# TinyGController.net
KiCad netlist of a schematic drawn in EAGLE
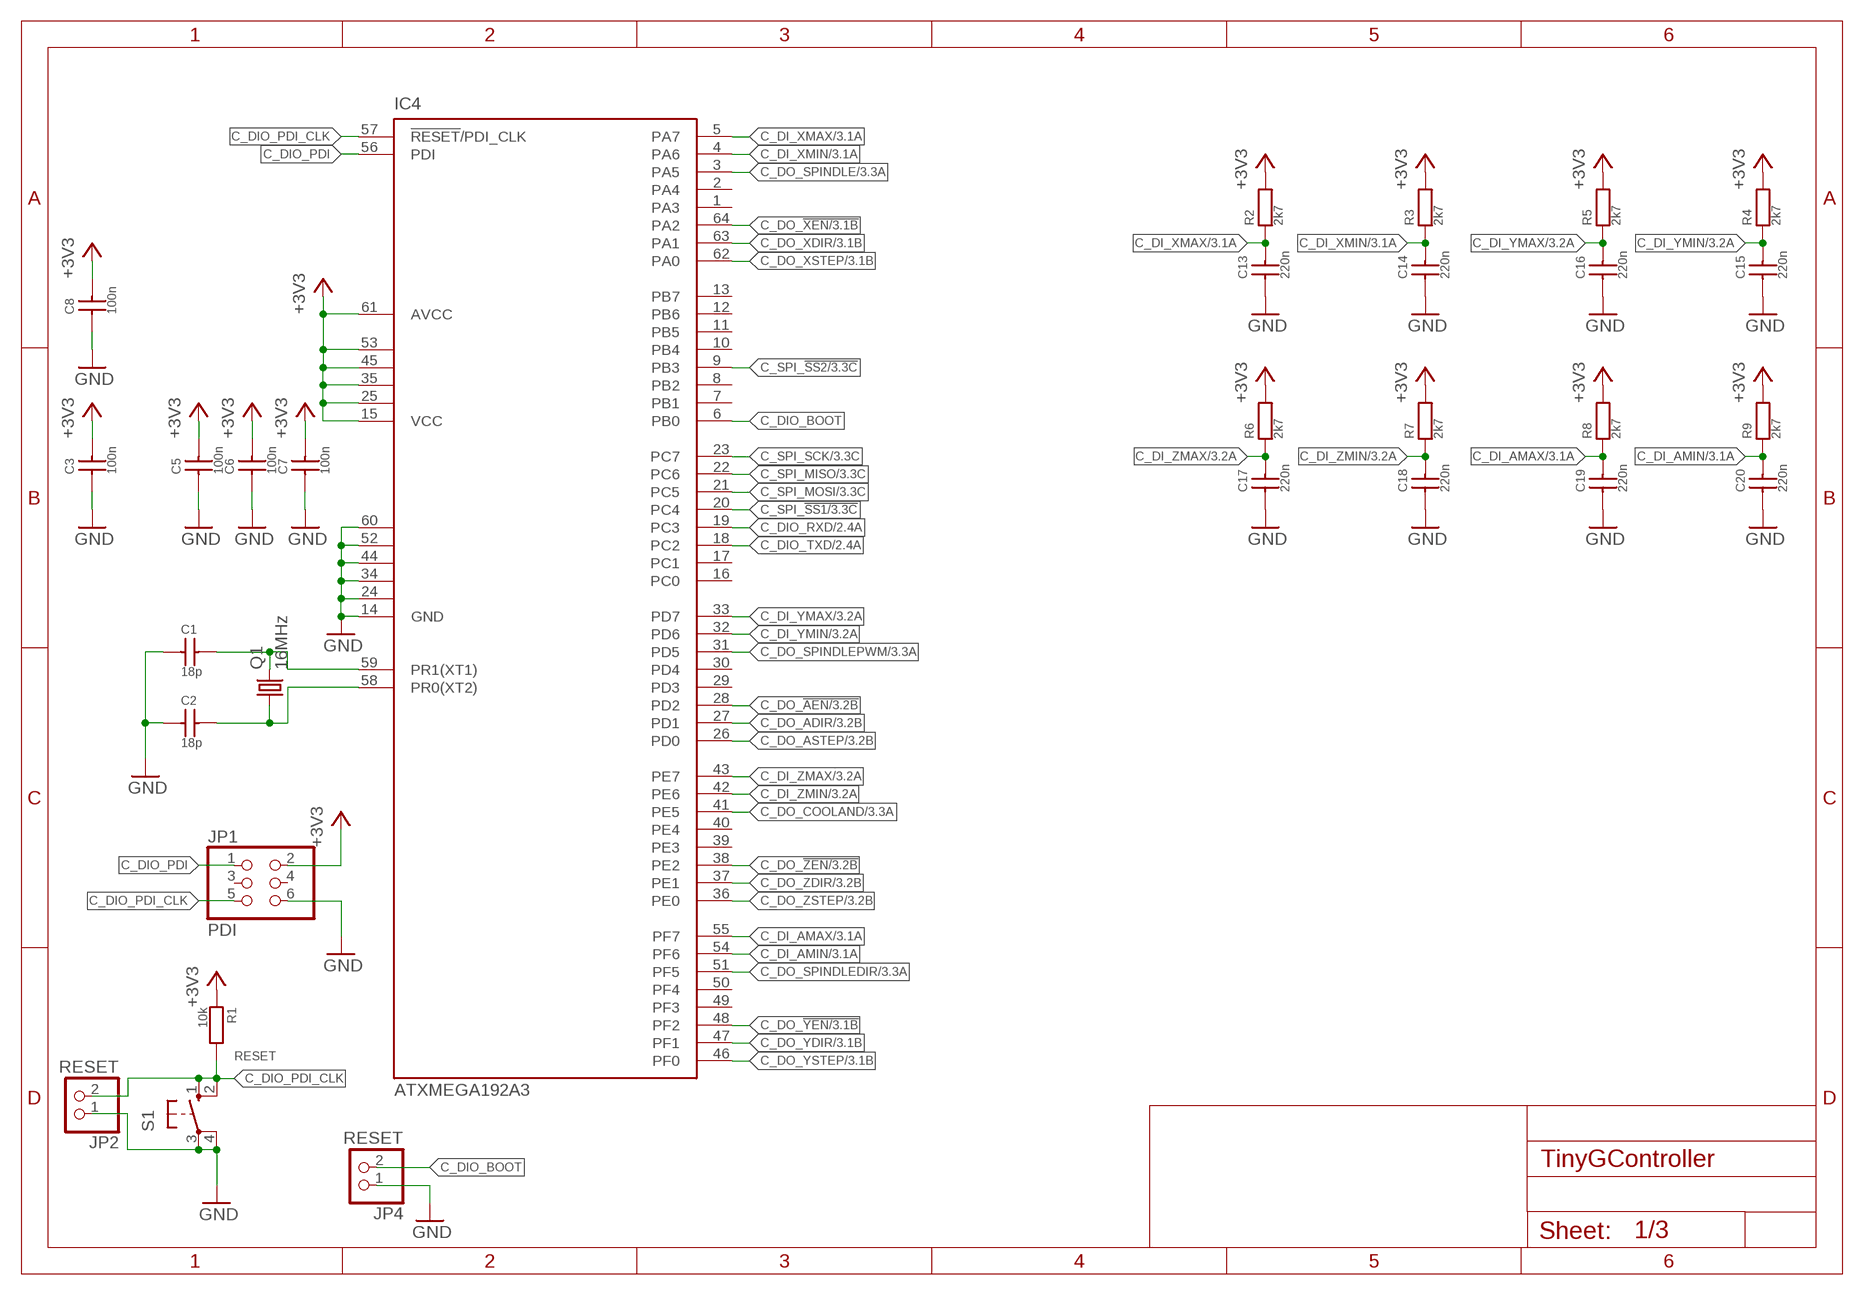
[diagram p0: schematic, sheet 1]
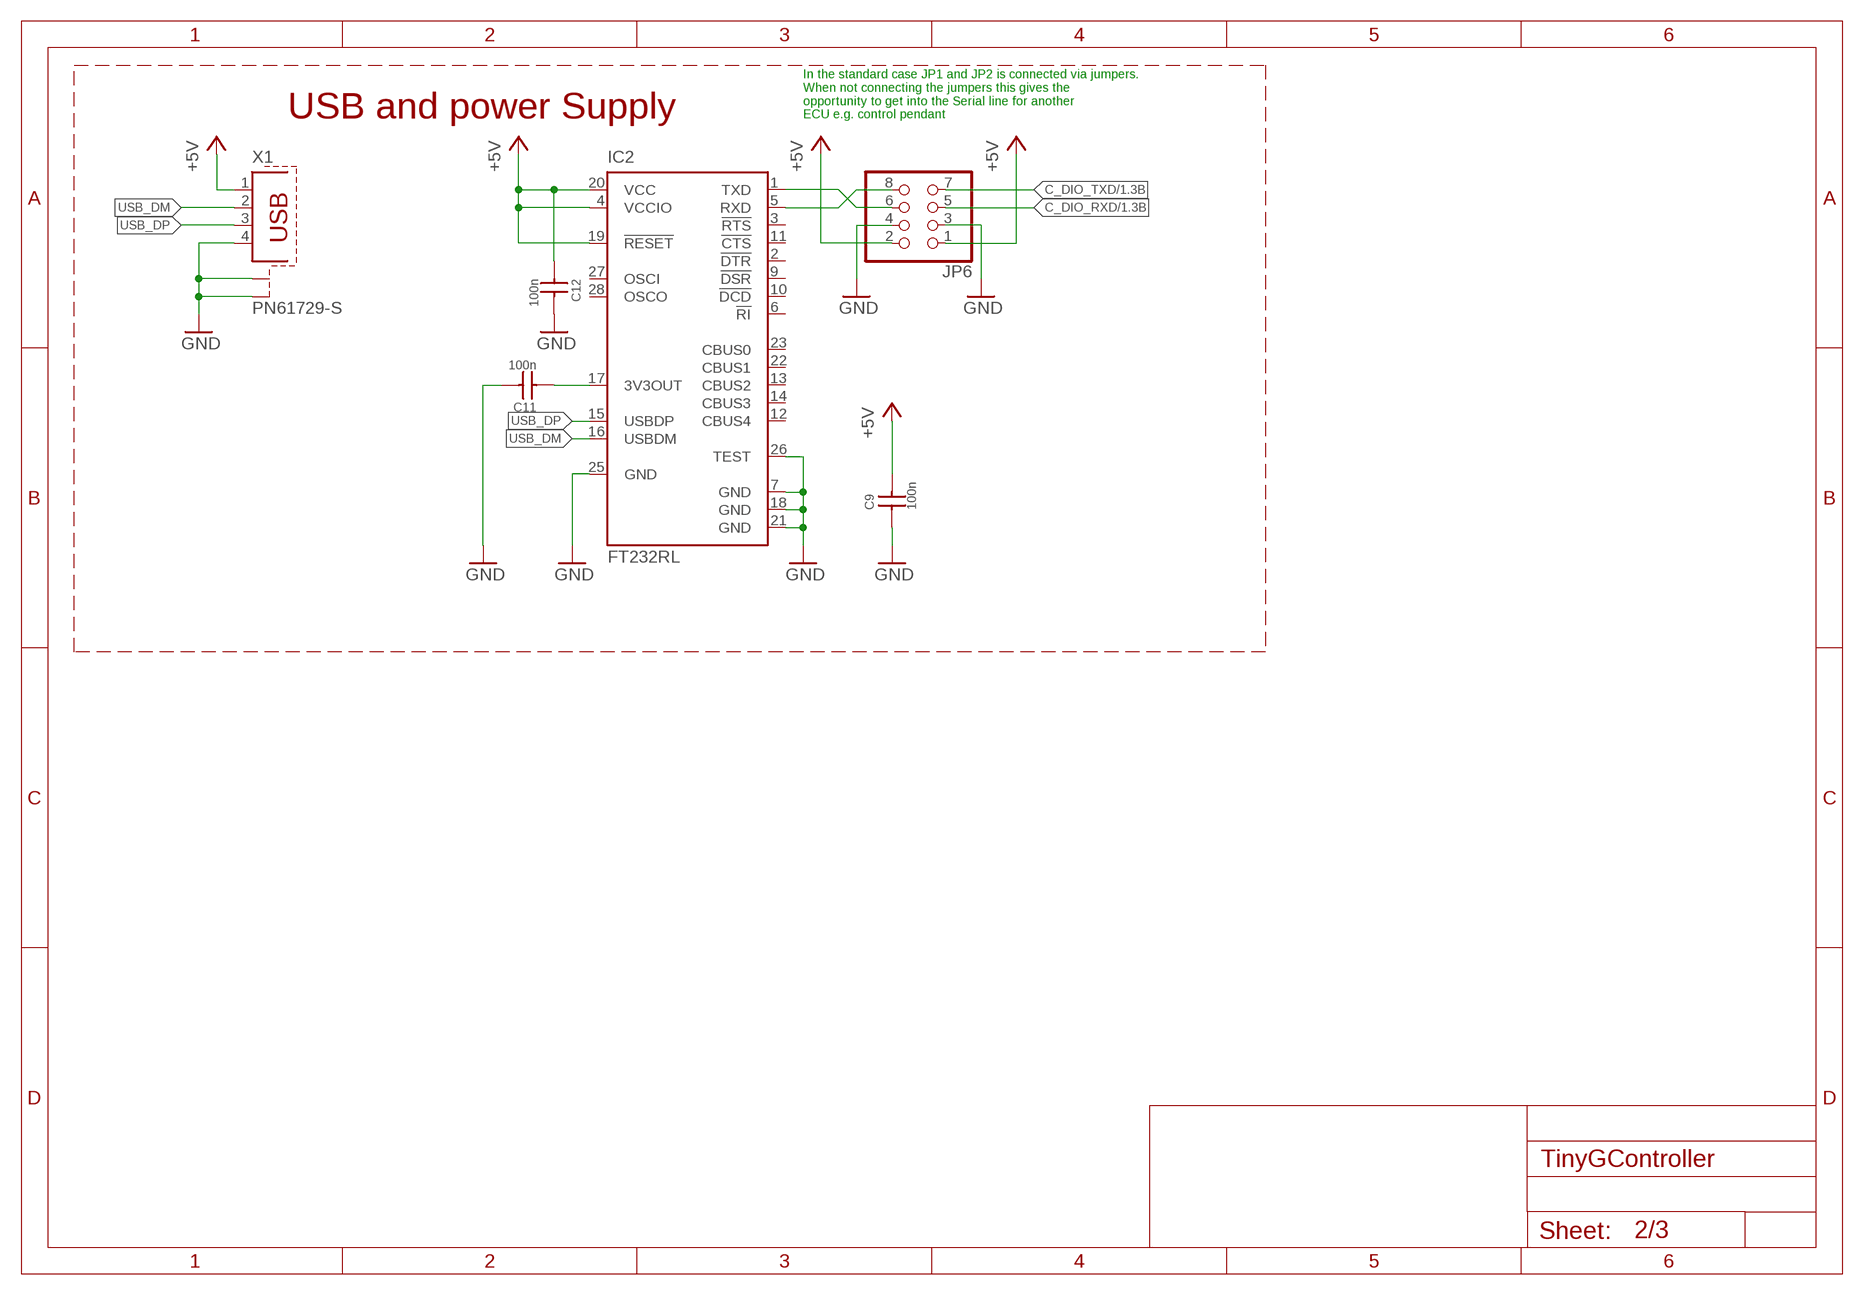
[diagram p1: schematic, sheet 2]
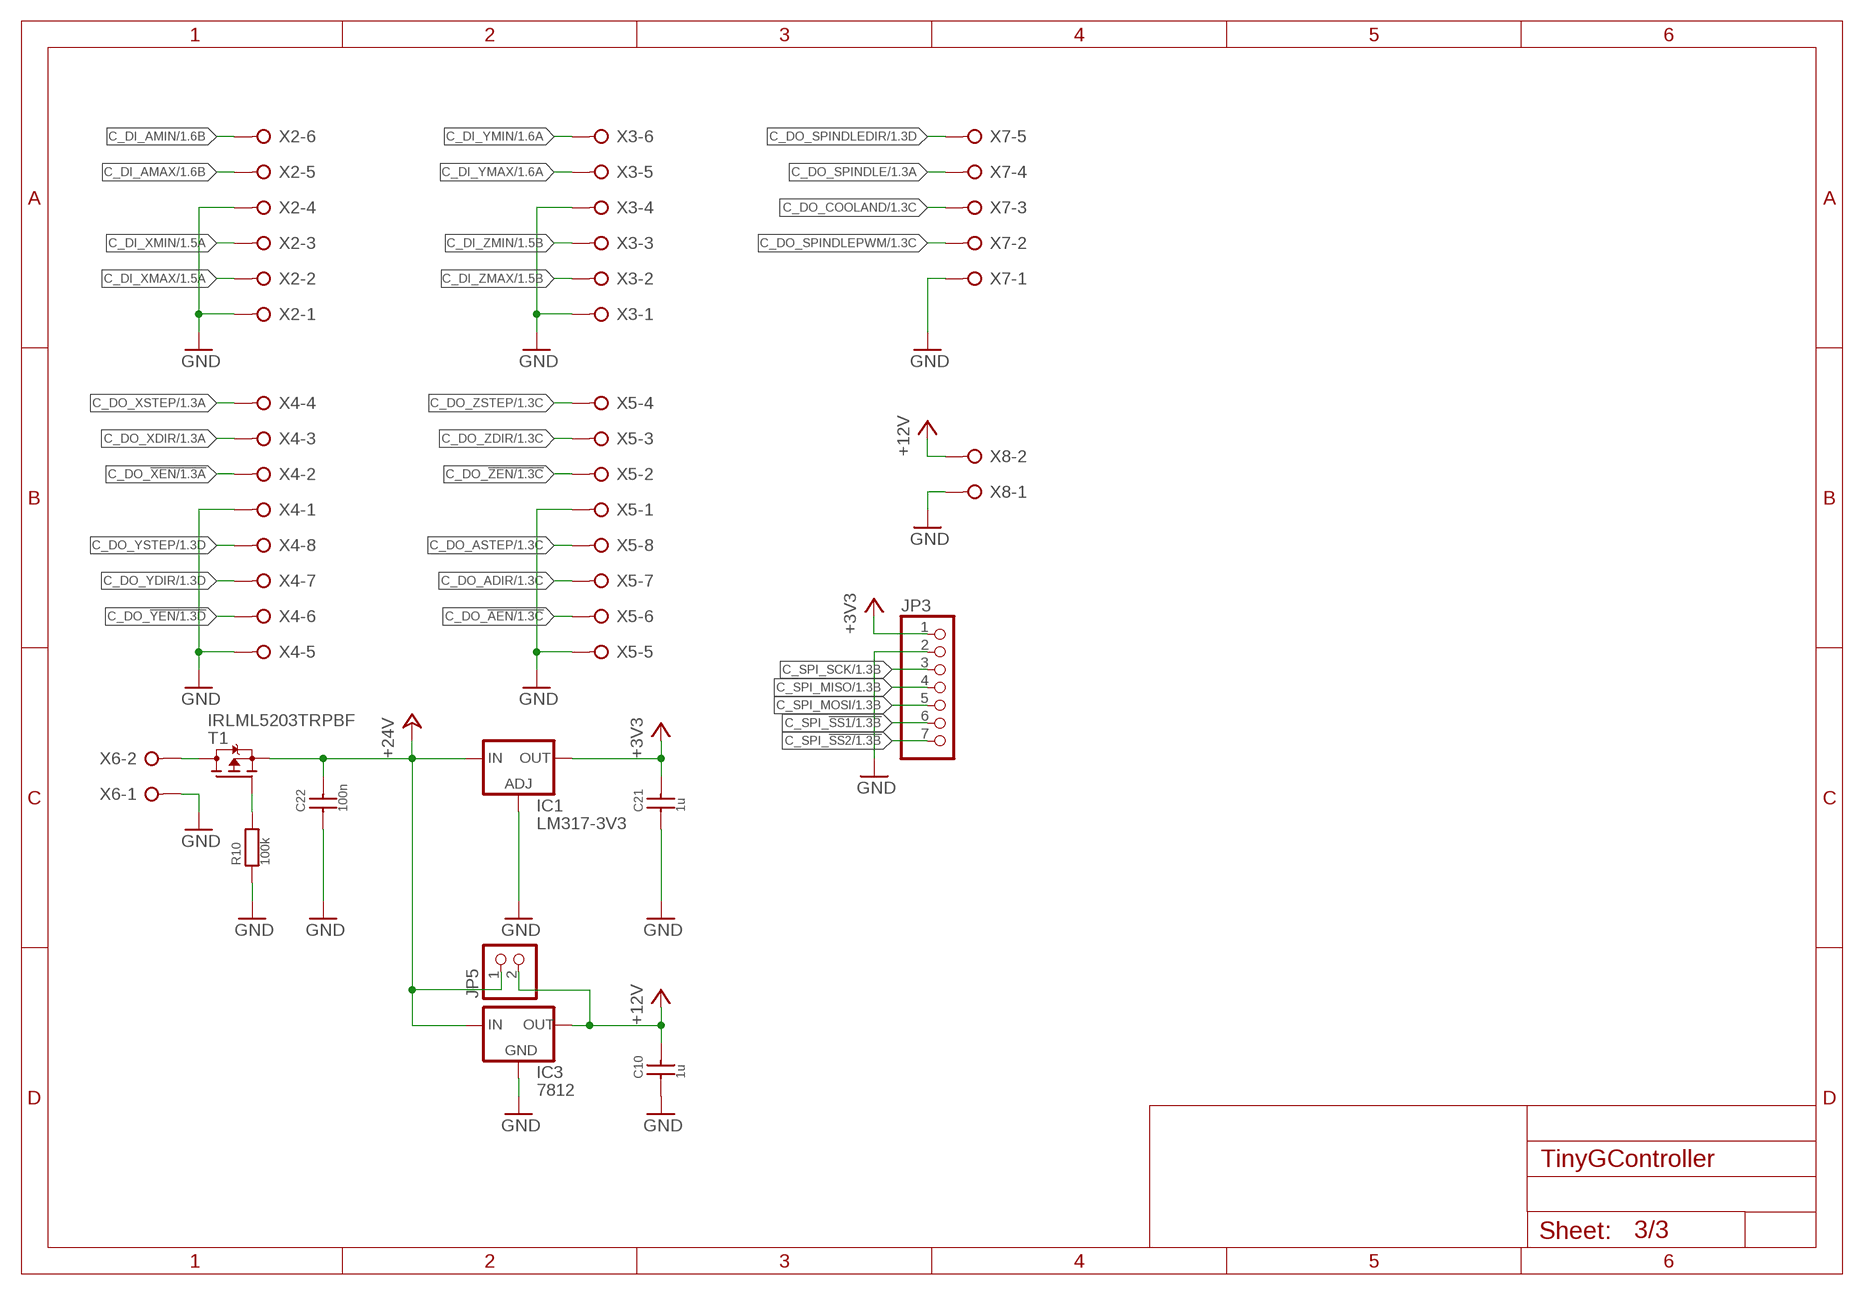
[diagram p2: schematic, sheet 3]

(export (version "E")
  (design (tool "Eeschema 10.0.6"))
  (components
    (comp (ref "C10")
      (value "1u")
      (footprint "eagle-import:C0805")
      (libsource (lib "eagle-import") (part "C_SMD0805"))
    )
    (comp (ref "C21")
      (value "1u")
      (footprint "eagle-import:C0805")
      (libsource (lib "eagle-import") (part "C_SMD0805"))
    )
    (comp (ref "C22")
      (value "100n")
      (footprint "eagle-import:C0805")
      (libsource (lib "eagle-import") (part "C_SMD0805"))
    )
    (comp (ref "IC1")
      (value "LM317-3V3")
      (footprint "eagle-import:SOT223")
      (libsource (lib "eagle-import") (part "LM317?MBSTT3"))
    )
    (comp (ref "IC3")
      (value "7812")
      (footprint "eagle-import:78XXS")
      (libsource (lib "eagle-import") (part "78XXS"))
    )
    (comp (ref "JP3")
      (value "PINHD-1X7")
      (footprint "eagle-import:1X07")
      (libsource (lib "eagle-import") (part "PINHD-1X7"))
    )
    (comp (ref "JP5")
      (value "PINHD-1X2")
      (footprint "eagle-import:1X02")
      (libsource (lib "eagle-import") (part "PINHD-1X2"))
    )
    (comp (ref "R10")
      (value "100k")
      (footprint "eagle-import:R0603")
      (libsource (lib "eagle-import") (part "R0603"))
    )
    (comp (ref "T1")
      (value "IRLML5203TRPBF")
      (footprint "eagle-import:SOT23")
      (libsource (lib "eagle-import") (part "IRLML5203TRPBF"))
    )
    (comp (ref "X2")
      (value "W237-06P")
      (footprint "eagle-import:W237-6P")
      (libsource (lib "eagle-import") (part "W237-06P"))
    )
    (comp (ref "X3")
      (value "W237-06P")
      (footprint "eagle-import:W237-6P")
      (libsource (lib "eagle-import") (part "W237-06P"))
    )
    (comp (ref "X4")
      (value "W237-08P")
      (footprint "eagle-import:W237-8P")
      (libsource (lib "eagle-import") (part "W237-08P"))
    )
    (comp (ref "X5")
      (value "W237-08P")
      (footprint "eagle-import:W237-8P")
      (libsource (lib "eagle-import") (part "W237-08P"))
    )
    (comp (ref "X6")
      (value "W237-02P")
      (footprint "eagle-import:W237-132")
      (libsource (lib "eagle-import") (part "W237-02P"))
    )
    (comp (ref "X7")
      (value "W237-05P")
      (footprint "eagle-import:W237-5P")
      (libsource (lib "eagle-import") (part "W237-05P"))
    )
    (comp (ref "X8")
      (value "W237-02P")
      (footprint "eagle-import:W237-132")
      (libsource (lib "eagle-import") (part "W237-02P"))
    )
    (comp (ref "C9")
      (value "100n")
      (footprint "eagle-import:C0603")
      (libsource (lib "eagle-import") (part "C_SMD0603"))
    )
    (comp (ref "C11")
      (value "100n")
      (footprint "eagle-import:C0603")
      (libsource (lib "eagle-import") (part "C_SMD0603"))
    )
    (comp (ref "C12")
      (value "100n")
      (footprint "eagle-import:C0603")
      (libsource (lib "eagle-import") (part "C_SMD0603"))
    )
    (comp (ref "IC2")
      (value "FT232RL")
      (footprint "eagle-import:SSOP28")
      (libsource (lib "eagle-import") (part "FT232RL"))
    )
    (comp (ref "JP6")
      (value "PINHD-2X4")
      (footprint "eagle-import:2X04")
      (libsource (lib "eagle-import") (part "PINHD-2X4"))
    )
    (comp (ref "X1")
      (value "PN61729-S")
      (footprint "eagle-import:PN61729-S")
      (libsource (lib "eagle-import") (part "PN61729-S"))
    )
    (comp (ref "C1")
      (value "18p")
      (footprint "eagle-import:C0603")
      (libsource (lib "eagle-import") (part "C_SMD0603"))
    )
    (comp (ref "C2")
      (value "18p")
      (footprint "eagle-import:C0603")
      (libsource (lib "eagle-import") (part "C_SMD0603"))
    )
    (comp (ref "C3")
      (value "100n")
      (footprint "eagle-import:C0603")
      (libsource (lib "eagle-import") (part "C_SMD0603"))
    )
    (comp (ref "C5")
      (value "100n")
      (footprint "eagle-import:C0603")
      (libsource (lib "eagle-import") (part "C_SMD0603"))
    )
    (comp (ref "C6")
      (value "100n")
      (footprint "eagle-import:C0603")
      (libsource (lib "eagle-import") (part "C_SMD0603"))
    )
    (comp (ref "C7")
      (value "100n")
      (footprint "eagle-import:C0603")
      (libsource (lib "eagle-import") (part "C_SMD0603"))
    )
    (comp (ref "C8")
      (value "100n")
      (footprint "eagle-import:C0603")
      (libsource (lib "eagle-import") (part "C_SMD0603"))
    )
    (comp (ref "C13")
      (value "220n")
      (footprint "eagle-import:C0805")
      (libsource (lib "eagle-import") (part "C_SMD0805"))
    )
    (comp (ref "C14")
      (value "220n")
      (footprint "eagle-import:C0805")
      (libsource (lib "eagle-import") (part "C_SMD0805"))
    )
    (comp (ref "C15")
      (value "220n")
      (footprint "eagle-import:C0805")
      (libsource (lib "eagle-import") (part "C_SMD0805"))
    )
    (comp (ref "C16")
      (value "220n")
      (footprint "eagle-import:C0805")
      (libsource (lib "eagle-import") (part "C_SMD0805"))
    )
    (comp (ref "C17")
      (value "220n")
      (footprint "eagle-import:C0805")
      (libsource (lib "eagle-import") (part "C_SMD0805"))
    )
    (comp (ref "C18")
      (value "220n")
      (footprint "eagle-import:C0805")
      (libsource (lib "eagle-import") (part "C_SMD0805"))
    )
    (comp (ref "C19")
      (value "220n")
      (footprint "eagle-import:C0805")
      (libsource (lib "eagle-import") (part "C_SMD0805"))
    )
    (comp (ref "C20")
      (value "220n")
      (footprint "eagle-import:C0805")
      (libsource (lib "eagle-import") (part "C_SMD0805"))
    )
    (comp (ref "IC4")
      (value "ATXMEGA192A3")
      (footprint "eagle-import:TQFP64-0.8MM")
      (libsource (lib "eagle-import") (part "ATXMEGA192A3"))
    )
    (comp (ref "JP1")
      (value "PDI")
      (footprint "eagle-import:2X03")
      (libsource (lib "eagle-import") (part "PINHD-2X3"))
    )
    (comp (ref "JP2")
      (value "RESET")
      (footprint "eagle-import:1X02")
      (libsource (lib "eagle-import") (part "PINHD-1X2"))
    )
    (comp (ref "JP4")
      (value "RESET")
      (footprint "eagle-import:1X02")
      (libsource (lib "eagle-import") (part "PINHD-1X2"))
    )
    (comp (ref "Q1")
      (value "16MHz")
      (footprint "eagle-import:HC49_USSM")
      (libsource (lib "eagle-import") (part "ATS073ASM-1"))
    )
    (comp (ref "R1")
      (value "10k")
      (footprint "eagle-import:R0603")
      (libsource (lib "eagle-import") (part "R0603"))
    )
    (comp (ref "R2")
      (value "2k7")
      (footprint "eagle-import:R0603")
      (libsource (lib "eagle-import") (part "R0603"))
    )
    (comp (ref "R3")
      (value "2k7")
      (footprint "eagle-import:R0603")
      (libsource (lib "eagle-import") (part "R0603"))
    )
    (comp (ref "R4")
      (value "2k7")
      (footprint "eagle-import:R0603")
      (libsource (lib "eagle-import") (part "R0603"))
    )
    (comp (ref "R5")
      (value "2k7")
      (footprint "eagle-import:R0603")
      (libsource (lib "eagle-import") (part "R0603"))
    )
    (comp (ref "R6")
      (value "2k7")
      (footprint "eagle-import:R0603")
      (libsource (lib "eagle-import") (part "R0603"))
    )
    (comp (ref "R7")
      (value "2k7")
      (footprint "eagle-import:R0603")
      (libsource (lib "eagle-import") (part "R0603"))
    )
    (comp (ref "R8")
      (value "2k7")
      (footprint "eagle-import:R0603")
      (libsource (lib "eagle-import") (part "R0603"))
    )
    (comp (ref "R9")
      (value "2k7")
      (footprint "eagle-import:R0603")
      (libsource (lib "eagle-import") (part "R0603"))
    )
    (comp (ref "S1")
      (value "10-XX")
      (footprint "eagle-import:B3F-10XX")
      (fields (field (name "MPN") "B3F-1000"))
      (libsource (lib "eagle-import") (part "10-XX"))
    )
  )
  (nets
    (net (code "1") (name "+3V3") (class "Default")
      (node (ref "C21") (pin "2") (pinfunction "P$2_2") (pintype "passive"))
      (node (ref "C3") (pin "2") (pinfunction "P$2_2") (pintype "passive"))
      (node (ref "C5") (pin "2") (pinfunction "P$2_2") (pintype "passive"))
      (node (ref "C6") (pin "2") (pinfunction "P$2_2") (pintype "passive"))
      (node (ref "C7") (pin "2") (pinfunction "P$2_2") (pintype "passive"))
      (node (ref "C8") (pin "2") (pinfunction "P$2_2") (pintype "passive"))
      (node (ref "IC1") (pin "4") (pinfunction "OUT_4") (pintype "passive"))
      (node (ref "IC4") (pin "15") (pinfunction "VCC_15") (pintype "power_in"))
      (node (ref "IC4") (pin "25") (pinfunction "VCC1_25") (pintype "power_in"))
      (node (ref "IC4") (pin "35") (pinfunction "VCC2_35") (pintype "power_in"))
      (node (ref "IC4") (pin "45") (pinfunction "VCC3_45") (pintype "power_in"))
      (node (ref "IC4") (pin "53") (pinfunction "VCC4_53") (pintype "power_in"))
      (node (ref "IC4") (pin "61") (pinfunction "AVCC_61") (pintype "power_in"))
      (node (ref "JP1") (pin "2") (pinfunction "2_2") (pintype "passive"))
      (node (ref "JP3") (pin "1") (pinfunction "1_1") (pintype "passive"))
      (node (ref "R1") (pin "1") (pinfunction "P$1_1") (pintype "passive"))
      (node (ref "R2") (pin "2") (pinfunction "P$2_2") (pintype "passive"))
      (node (ref "R3") (pin "2") (pinfunction "P$2_2") (pintype "passive"))
      (node (ref "R4") (pin "2") (pinfunction "P$2_2") (pintype "passive"))
      (node (ref "R5") (pin "2") (pinfunction "P$2_2") (pintype "passive"))
      (node (ref "R6") (pin "2") (pinfunction "P$2_2") (pintype "passive"))
      (node (ref "R7") (pin "2") (pinfunction "P$2_2") (pintype "passive"))
      (node (ref "R8") (pin "2") (pinfunction "P$2_2") (pintype "passive"))
      (node (ref "R9") (pin "2") (pinfunction "P$2_2") (pintype "passive"))
    )
    (net (code "2") (name "+5V") (class "Default")
      (node (ref "C12") (pin "1") (pinfunction "P$1_1") (pintype "passive"))
      (node (ref "C9") (pin "2") (pinfunction "P$2_2") (pintype "passive"))
      (node (ref "IC2") (pin "19") (pinfunction "~{RESET}_19") (pintype "input"))
      (node (ref "IC2") (pin "20") (pinfunction "VCC_20") (pintype "power_in"))
      (node (ref "IC2") (pin "4") (pinfunction "VCCIO_4") (pintype "power_in"))
      (node (ref "JP6") (pin "1") (pinfunction "1_1") (pintype "passive"))
      (node (ref "JP6") (pin "2") (pinfunction "2_2") (pintype "passive"))
      (node (ref "X1") (pin "1") (pinfunction "1_1") (pintype "passive"))
    )
    (net (code "3") (name "+12V") (class "Default")
      (node (ref "C10") (pin "2") (pinfunction "P$2_2") (pintype "passive"))
      (node (ref "IC3") (pin "OUT") (pinfunction "OUT_OUT") (pintype "passive"))
      (node (ref "JP5") (pin "2") (pinfunction "2_2") (pintype "passive"))
      (node (ref "X8") (pin "2") (pinfunction "KL_2") (pintype "passive"))
    )
    (net (code "4") (name "+24V") (class "Default")
      (node (ref "C22") (pin "2") (pinfunction "P$2_2") (pintype "passive"))
      (node (ref "IC1") (pin "3") (pinfunction "IN_3") (pintype "input"))
      (node (ref "IC3") (pin "IN") (pinfunction "IN_IN") (pintype "input"))
      (node (ref "JP5") (pin "1") (pinfunction "1_1") (pintype "passive"))
      (node (ref "T1") (pin "2") (pinfunction "S_2") (pintype "passive"))
    )
    (net (code "5") (name "C_DIO_BOOT") (class "Default")
      (node (ref "IC4") (pin "6") (pinfunction "PB0_6") (pintype "bidirectional"))
      (node (ref "JP4") (pin "2") (pinfunction "2_2") (pintype "passive"))
    )
    (net (code "6") (name "C_DIO_PDI") (class "Default")
      (node (ref "IC4") (pin "56") (pinfunction "PDI_56") (pintype "input"))
      (node (ref "JP1") (pin "1") (pinfunction "1_1") (pintype "passive"))
    )
    (net (code "7") (name "C_DIO_PDI_CLK") (class "Default")
      (node (ref "IC4") (pin "57") (pinfunction "~{RESET}/PDI_CLK_57") (pintype "input"))
      (node (ref "JP1") (pin "5") (pinfunction "5_5") (pintype "passive"))
      (node (ref "JP2") (pin "2") (pinfunction "2_2") (pintype "passive"))
      (node (ref "R1") (pin "2") (pinfunction "P$2_2") (pintype "passive"))
      (node (ref "S1") (pin "1") (pinfunction "S_1") (pintype "passive"))
      (node (ref "S1") (pin "2") (pinfunction "S1_2") (pintype "passive"))
    )
    (net (code "8") (name "C_DIO_RXD") (class "Default")
      (node (ref "IC4") (pin "19") (pinfunction "PC3_19") (pintype "bidirectional"))
      (node (ref "JP6") (pin "5") (pinfunction "5_5") (pintype "passive"))
    )
    (net (code "9") (name "C_DIO_TXD") (class "Default")
      (node (ref "IC4") (pin "18") (pinfunction "PC2_18") (pintype "bidirectional"))
      (node (ref "JP6") (pin "7") (pinfunction "7_7") (pintype "passive"))
    )
    (net (code "10") (name "C_DI_AMAX") (class "Default")
      (node (ref "C19") (pin "2") (pinfunction "P$2_2") (pintype "passive"))
      (node (ref "IC4") (pin "55") (pinfunction "PF7_55") (pintype "bidirectional"))
      (node (ref "R8") (pin "1") (pinfunction "P$1_1") (pintype "passive"))
      (node (ref "X2") (pin "5") (pinfunction "KL_5") (pintype "passive"))
    )
    (net (code "11") (name "C_DI_AMIN") (class "Default")
      (node (ref "C20") (pin "2") (pinfunction "P$2_2") (pintype "passive"))
      (node (ref "IC4") (pin "54") (pinfunction "PF6_54") (pintype "bidirectional"))
      (node (ref "R9") (pin "1") (pinfunction "P$1_1") (pintype "passive"))
      (node (ref "X2") (pin "6") (pinfunction "KL_6") (pintype "passive"))
    )
    (net (code "12") (name "C_DI_XMAX") (class "Default")
      (node (ref "C13") (pin "2") (pinfunction "P$2_2") (pintype "passive"))
      (node (ref "IC4") (pin "5") (pinfunction "PA7_5") (pintype "bidirectional"))
      (node (ref "R2") (pin "1") (pinfunction "P$1_1") (pintype "passive"))
      (node (ref "X2") (pin "2") (pinfunction "KL_2") (pintype "passive"))
    )
    (net (code "13") (name "C_DI_XMIN") (class "Default")
      (node (ref "C14") (pin "2") (pinfunction "P$2_2") (pintype "passive"))
      (node (ref "IC4") (pin "4") (pinfunction "PA6_4") (pintype "bidirectional"))
      (node (ref "R3") (pin "1") (pinfunction "P$1_1") (pintype "passive"))
      (node (ref "X2") (pin "3") (pinfunction "KL_3") (pintype "passive"))
    )
    (net (code "14") (name "C_DI_YMAX") (class "Default")
      (node (ref "C16") (pin "2") (pinfunction "P$2_2") (pintype "passive"))
      (node (ref "IC4") (pin "33") (pinfunction "PD7_33") (pintype "bidirectional"))
      (node (ref "R5") (pin "1") (pinfunction "P$1_1") (pintype "passive"))
      (node (ref "X3") (pin "5") (pinfunction "KL_5") (pintype "passive"))
    )
    (net (code "15") (name "C_DI_YMIN") (class "Default")
      (node (ref "C15") (pin "2") (pinfunction "P$2_2") (pintype "passive"))
      (node (ref "IC4") (pin "32") (pinfunction "PD6_32") (pintype "bidirectional"))
      (node (ref "R4") (pin "1") (pinfunction "P$1_1") (pintype "passive"))
      (node (ref "X3") (pin "6") (pinfunction "KL_6") (pintype "passive"))
    )
    (net (code "16") (name "C_DI_ZMAX") (class "Default")
      (node (ref "C17") (pin "2") (pinfunction "P$2_2") (pintype "passive"))
      (node (ref "IC4") (pin "43") (pinfunction "PE7_43") (pintype "bidirectional"))
      (node (ref "R6") (pin "1") (pinfunction "P$1_1") (pintype "passive"))
      (node (ref "X3") (pin "2") (pinfunction "KL_2") (pintype "passive"))
    )
    (net (code "17") (name "C_DI_ZMIN") (class "Default")
      (node (ref "C18") (pin "2") (pinfunction "P$2_2") (pintype "passive"))
      (node (ref "IC4") (pin "42") (pinfunction "PE6_42") (pintype "bidirectional"))
      (node (ref "R7") (pin "1") (pinfunction "P$1_1") (pintype "passive"))
      (node (ref "X3") (pin "3") (pinfunction "KL_3") (pintype "passive"))
    )
    (net (code "18") (name "C_DO_ADIR") (class "Default")
      (node (ref "IC4") (pin "27") (pinfunction "PD1_27") (pintype "bidirectional"))
      (node (ref "X5") (pin "7") (pinfunction "KL_7") (pintype "passive"))
    )
    (net (code "19") (name "C_DO_ASTEP") (class "Default")
      (node (ref "IC4") (pin "26") (pinfunction "PD0_26") (pintype "bidirectional"))
      (node (ref "X5") (pin "8") (pinfunction "KL_8") (pintype "passive"))
    )
    (net (code "20") (name "C_DO_COOLAND") (class "Default")
      (node (ref "IC4") (pin "41") (pinfunction "PE5_41") (pintype "bidirectional"))
      (node (ref "X7") (pin "3") (pinfunction "KL_3") (pintype "passive"))
    )
    (net (code "21") (name "C_DO_SPINDLE") (class "Default")
      (node (ref "IC4") (pin "3") (pinfunction "PA5_3") (pintype "bidirectional"))
      (node (ref "X7") (pin "4") (pinfunction "KL_4") (pintype "passive"))
    )
    (net (code "22") (name "C_DO_SPINDLEDIR") (class "Default")
      (node (ref "IC4") (pin "51") (pinfunction "PF5_51") (pintype "bidirectional"))
      (node (ref "X7") (pin "5") (pinfunction "KL_5") (pintype "passive"))
    )
    (net (code "23") (name "C_DO_SPINDLEPWM") (class "Default")
      (node (ref "IC4") (pin "31") (pinfunction "PD5_31") (pintype "bidirectional"))
      (node (ref "X7") (pin "2") (pinfunction "KL_2") (pintype "passive"))
    )
    (net (code "24") (name "C_DO_XDIR") (class "Default")
      (node (ref "IC4") (pin "63") (pinfunction "PA1_63") (pintype "bidirectional"))
      (node (ref "X4") (pin "3") (pinfunction "KL_3") (pintype "passive"))
    )
    (net (code "25") (name "C_DO_XSTEP") (class "Default")
      (node (ref "IC4") (pin "62") (pinfunction "PA0_62") (pintype "bidirectional"))
      (node (ref "X4") (pin "4") (pinfunction "KL_4") (pintype "passive"))
    )
    (net (code "26") (name "C_DO_YDIR") (class "Default")
      (node (ref "IC4") (pin "47") (pinfunction "PF1_47") (pintype "bidirectional"))
      (node (ref "X4") (pin "7") (pinfunction "KL_7") (pintype "passive"))
    )
    (net (code "27") (name "C_DO_YSTEP") (class "Default")
      (node (ref "IC4") (pin "46") (pinfunction "PF0_46") (pintype "bidirectional"))
      (node (ref "X4") (pin "8") (pinfunction "KL_8") (pintype "passive"))
    )
    (net (code "28") (name "C_DO_ZDIR") (class "Default")
      (node (ref "IC4") (pin "37") (pinfunction "PE1_37") (pintype "bidirectional"))
      (node (ref "X5") (pin "3") (pinfunction "KL_3") (pintype "passive"))
    )
    (net (code "29") (name "C_DO_ZSTEP") (class "Default")
      (node (ref "IC4") (pin "36") (pinfunction "PE0_36") (pintype "bidirectional"))
      (node (ref "X5") (pin "4") (pinfunction "KL_4") (pintype "passive"))
    )
    (net (code "30") (name "C_DO_~{AEN}") (class "Default")
      (node (ref "IC4") (pin "28") (pinfunction "PD2_28") (pintype "bidirectional"))
      (node (ref "X5") (pin "6") (pinfunction "KL_6") (pintype "passive"))
    )
    (net (code "31") (name "C_DO_~{XEN}") (class "Default")
      (node (ref "IC4") (pin "64") (pinfunction "PA2_64") (pintype "bidirectional"))
      (node (ref "X4") (pin "2") (pinfunction "KL_2") (pintype "passive"))
    )
    (net (code "32") (name "C_DO_~{YEN}") (class "Default")
      (node (ref "IC4") (pin "48") (pinfunction "PF2_48") (pintype "bidirectional"))
      (node (ref "X4") (pin "6") (pinfunction "KL_6") (pintype "passive"))
    )
    (net (code "33") (name "C_DO_~{ZEN}") (class "Default")
      (node (ref "IC4") (pin "38") (pinfunction "PE2_38") (pintype "bidirectional"))
      (node (ref "X5") (pin "2") (pinfunction "KL_2") (pintype "passive"))
    )
    (net (code "34") (name "C_SPI_MISO") (class "Default")
      (node (ref "IC4") (pin "22") (pinfunction "PC6_22") (pintype "bidirectional"))
      (node (ref "JP3") (pin "4") (pinfunction "4_4") (pintype "passive"))
    )
    (net (code "35") (name "C_SPI_MOSI") (class "Default")
      (node (ref "IC4") (pin "21") (pinfunction "PC5_21") (pintype "bidirectional"))
      (node (ref "JP3") (pin "5") (pinfunction "5_5") (pintype "passive"))
    )
    (net (code "36") (name "C_SPI_SCK") (class "Default")
      (node (ref "IC4") (pin "23") (pinfunction "PC7_23") (pintype "bidirectional"))
      (node (ref "JP3") (pin "3") (pinfunction "3_3") (pintype "passive"))
    )
    (net (code "37") (name "C_SPI_~{SS1}") (class "Default")
      (node (ref "IC4") (pin "20") (pinfunction "PC4_20") (pintype "bidirectional"))
      (node (ref "JP3") (pin "6") (pinfunction "6_6") (pintype "passive"))
    )
    (net (code "38") (name "C_SPI_~{SS2}") (class "Default")
      (node (ref "IC4") (pin "9") (pinfunction "PB3_9") (pintype "bidirectional"))
      (node (ref "JP3") (pin "7") (pinfunction "7_7") (pintype "passive"))
    )
    (net (code "39") (name "GND") (class "Default")
      (node (ref "C1") (pin "1") (pinfunction "P$1_1") (pintype "passive"))
      (node (ref "C10") (pin "1") (pinfunction "P$1_1") (pintype "passive"))
      (node (ref "C11") (pin "2") (pinfunction "P$2_2") (pintype "passive"))
      (node (ref "C12") (pin "2") (pinfunction "P$2_2") (pintype "passive"))
      (node (ref "C13") (pin "1") (pinfunction "P$1_1") (pintype "passive"))
      (node (ref "C14") (pin "1") (pinfunction "P$1_1") (pintype "passive"))
      (node (ref "C15") (pin "1") (pinfunction "P$1_1") (pintype "passive"))
      (node (ref "C16") (pin "1") (pinfunction "P$1_1") (pintype "passive"))
      (node (ref "C17") (pin "1") (pinfunction "P$1_1") (pintype "passive"))
      (node (ref "C18") (pin "1") (pinfunction "P$1_1") (pintype "passive"))
      (node (ref "C19") (pin "1") (pinfunction "P$1_1") (pintype "passive"))
      (node (ref "C2") (pin "1") (pinfunction "P$1_1") (pintype "passive"))
      (node (ref "C20") (pin "1") (pinfunction "P$1_1") (pintype "passive"))
      (node (ref "C21") (pin "1") (pinfunction "P$1_1") (pintype "passive"))
      (node (ref "C22") (pin "1") (pinfunction "P$1_1") (pintype "passive"))
      (node (ref "C3") (pin "1") (pinfunction "P$1_1") (pintype "passive"))
      (node (ref "C5") (pin "1") (pinfunction "P$1_1") (pintype "passive"))
      (node (ref "C6") (pin "1") (pinfunction "P$1_1") (pintype "passive"))
      (node (ref "C7") (pin "1") (pinfunction "P$1_1") (pintype "passive"))
      (node (ref "C8") (pin "1") (pinfunction "P$1_1") (pintype "passive"))
      (node (ref "C9") (pin "1") (pinfunction "P$1_1") (pintype "passive"))
      (node (ref "IC1") (pin "1") (pinfunction "ADJ_1") (pintype "input"))
      (node (ref "IC2") (pin "18") (pinfunction "GND_18") (pintype "power_in"))
      (node (ref "IC2") (pin "21") (pinfunction "GND_21") (pintype "power_in"))
      (node (ref "IC2") (pin "25") (pinfunction "GND_25") (pintype "power_in"))
      (node (ref "IC2") (pin "26") (pinfunction "TEST_26") (pintype "input"))
      (node (ref "IC2") (pin "7") (pinfunction "GND_7") (pintype "power_in"))
      (node (ref "IC3") (pin "GND") (pinfunction "GND_GND") (pintype "input"))
      (node (ref "IC4") (pin "14") (pinfunction "GND_14") (pintype "power_in"))
      (node (ref "IC4") (pin "24") (pinfunction "GND1_24") (pintype "power_in"))
      (node (ref "IC4") (pin "34") (pinfunction "GND2_34") (pintype "power_in"))
      (node (ref "IC4") (pin "44") (pinfunction "GND3_44") (pintype "power_in"))
      (node (ref "IC4") (pin "52") (pinfunction "GND4_52") (pintype "power_in"))
      (node (ref "IC4") (pin "60") (pinfunction "GND5_60") (pintype "power_in"))
      (node (ref "JP1") (pin "6") (pinfunction "6_6") (pintype "passive"))
      (node (ref "JP2") (pin "1") (pinfunction "1_1") (pintype "passive"))
      (node (ref "JP3") (pin "2") (pinfunction "2_2") (pintype "passive"))
      (node (ref "JP4") (pin "1") (pinfunction "1_1") (pintype "passive"))
      (node (ref "JP6") (pin "3") (pinfunction "3_3") (pintype "passive"))
      (node (ref "JP6") (pin "4") (pinfunction "4_4") (pintype "passive"))
      (node (ref "R10") (pin "1") (pinfunction "P$1_1") (pintype "passive"))
      (node (ref "S1") (pin "3") (pinfunction "P_3") (pintype "passive"))
      (node (ref "S1") (pin "4") (pinfunction "P1_4") (pintype "passive"))
      (node (ref "X1") (pin "4") (pinfunction "4_4") (pintype "passive"))
      (node (ref "X1") (pin "S1") (pinfunction "S1_S1") (pintype "passive"))
      (node (ref "X1") (pin "S2") (pinfunction "S2_S2") (pintype "passive"))
      (node (ref "X2") (pin "1") (pinfunction "KL_1") (pintype "passive"))
      (node (ref "X2") (pin "4") (pinfunction "KL_4") (pintype "passive"))
      (node (ref "X3") (pin "1") (pinfunction "KL_1") (pintype "passive"))
      (node (ref "X3") (pin "4") (pinfunction "KL_4") (pintype "passive"))
      (node (ref "X4") (pin "1") (pinfunction "KL_1") (pintype "passive"))
      (node (ref "X4") (pin "5") (pinfunction "KL_5") (pintype "passive"))
      (node (ref "X5") (pin "1") (pinfunction "KL_1") (pintype "passive"))
      (node (ref "X5") (pin "5") (pinfunction "KL_5") (pintype "passive"))
      (node (ref "X6") (pin "1") (pinfunction "KL_1") (pintype "passive"))
      (node (ref "X7") (pin "1") (pinfunction "KL_1") (pintype "passive"))
      (node (ref "X8") (pin "1") (pinfunction "KL_1") (pintype "passive"))
    )
    (net (code "40") (name "Net-(C1-P$2)") (class "Default")
      (node (ref "C1") (pin "2") (pinfunction "P$2_2") (pintype "passive"))
      (node (ref "IC4") (pin "59") (pinfunction "PR1(XT1)_59") (pintype "bidirectional"))
      (node (ref "Q1") (pin "2") (pinfunction "2_2") (pintype "passive"))
    )
    (net (code "41") (name "Net-(C2-P$2)") (class "Default")
      (node (ref "C2") (pin "2") (pinfunction "P$2_2") (pintype "passive"))
      (node (ref "IC4") (pin "58") (pinfunction "PR0(XT2)_58") (pintype "bidirectional"))
      (node (ref "Q1") (pin "1") (pinfunction "1_1") (pintype "passive"))
    )
    (net (code "42") (name "Net-(C11-P$1)") (class "Default")
      (node (ref "C11") (pin "1") (pinfunction "P$1_1") (pintype "passive"))
      (node (ref "IC2") (pin "17") (pinfunction "3V3OUT_17") (pintype "output"))
    )
    (net (code "43") (name "Net-(IC2-RXD)") (class "Default")
      (node (ref "IC2") (pin "5") (pinfunction "RXD_5") (pintype "input"))
      (node (ref "JP6") (pin "8") (pinfunction "8_8") (pintype "passive"))
    )
    (net (code "44") (name "Net-(IC2-TXD)") (class "Default")
      (node (ref "IC2") (pin "1") (pinfunction "TXD_1") (pintype "output"))
      (node (ref "JP6") (pin "6") (pinfunction "6_6") (pintype "passive"))
    )
    (net (code "45") (name "Net-(R10-P$2)") (class "Default")
      (node (ref "R10") (pin "2") (pinfunction "P$2_2") (pintype "passive"))
      (node (ref "T1") (pin "1") (pinfunction "G_1") (pintype "passive"))
    )
    (net (code "46") (name "Net-(T1-D)") (class "Default")
      (node (ref "T1") (pin "3") (pinfunction "D_3") (pintype "passive"))
      (node (ref "X6") (pin "2") (pinfunction "KL_2") (pintype "passive"))
    )
    (net (code "47") (name "USB_DM") (class "Default")
      (node (ref "IC2") (pin "16") (pinfunction "USBDM_16") (pintype "bidirectional"))
      (node (ref "X1") (pin "2") (pinfunction "2_2") (pintype "passive"))
    )
    (net (code "48") (name "USB_DP") (class "Default")
      (node (ref "IC2") (pin "15") (pinfunction "USBDP_15") (pintype "bidirectional"))
      (node (ref "X1") (pin "3") (pinfunction "3_3") (pintype "passive"))
    )
    (net (code "49") (name "unconnected-(IC2-CBUS0-Pad23)") (class "Default")
      (node (ref "IC2") (pin "23") (pinfunction "CBUS0_23") (pintype "bidirectional"))
    )
    (net (code "50") (name "unconnected-(IC2-CBUS1-Pad22)") (class "Default")
      (node (ref "IC2") (pin "22") (pinfunction "CBUS1_22") (pintype "bidirectional"))
    )
    (net (code "51") (name "unconnected-(IC2-CBUS2-Pad13)") (class "Default")
      (node (ref "IC2") (pin "13") (pinfunction "CBUS2_13") (pintype "bidirectional"))
    )
    (net (code "52") (name "unconnected-(IC2-CBUS3-Pad14)") (class "Default")
      (node (ref "IC2") (pin "14") (pinfunction "CBUS3_14") (pintype "bidirectional"))
    )
    (net (code "53") (name "unconnected-(IC2-CBUS4-Pad12)") (class "Default")
      (node (ref "IC2") (pin "12") (pinfunction "CBUS4_12") (pintype "bidirectional"))
    )
    (net (code "54") (name "unconnected-(IC2-OSCI-Pad27)") (class "Default")
      (node (ref "IC2") (pin "27") (pinfunction "OSCI_27") (pintype "input"))
    )
    (net (code "55") (name "unconnected-(IC2-OSCO-Pad28)") (class "Default")
      (node (ref "IC2") (pin "28") (pinfunction "OSCO_28") (pintype "output"))
    )
    (net (code "56") (name "unconnected-(IC2-~{CTS}-Pad11)") (class "Default")
      (node (ref "IC2") (pin "11") (pinfunction "~{CTS}_11") (pintype "input"))
    )
    (net (code "57") (name "unconnected-(IC2-~{DCD}-Pad10)") (class "Default")
      (node (ref "IC2") (pin "10") (pinfunction "~{DCD}_10") (pintype "input"))
    )
    (net (code "58") (name "unconnected-(IC2-~{DSR}-Pad9)") (class "Default")
      (node (ref "IC2") (pin "9") (pinfunction "~{DSR}_9") (pintype "input"))
    )
    (net (code "59") (name "unconnected-(IC2-~{DTR}-Pad2)") (class "Default")
      (node (ref "IC2") (pin "2") (pinfunction "~{DTR}_2") (pintype "output"))
    )
    (net (code "60") (name "unconnected-(IC2-~{RI}-Pad6)") (class "Default")
      (node (ref "IC2") (pin "6") (pinfunction "~{RI}_6") (pintype "input"))
    )
    (net (code "61") (name "unconnected-(IC2-~{RTS}-Pad3)") (class "Default")
      (node (ref "IC2") (pin "3") (pinfunction "~{RTS}_3") (pintype "output"))
    )
    (net (code "62") (name "unconnected-(IC4-PA3-Pad1)") (class "Default")
      (node (ref "IC4") (pin "1") (pinfunction "PA3_1") (pintype "bidirectional"))
    )
    (net (code "63") (name "unconnected-(IC4-PA4-Pad2)") (class "Default")
      (node (ref "IC4") (pin "2") (pinfunction "PA4_2") (pintype "bidirectional"))
    )
    (net (code "64") (name "unconnected-(IC4-PB1-Pad7)") (class "Default")
      (node (ref "IC4") (pin "7") (pinfunction "PB1_7") (pintype "bidirectional"))
    )
    (net (code "65") (name "unconnected-(IC4-PB2-Pad8)") (class "Default")
      (node (ref "IC4") (pin "8") (pinfunction "PB2_8") (pintype "bidirectional"))
    )
    (net (code "66") (name "unconnected-(IC4-PB4-Pad10)") (class "Default")
      (node (ref "IC4") (pin "10") (pinfunction "PB4_10") (pintype "bidirectional"))
    )
    (net (code "67") (name "unconnected-(IC4-PB5-Pad11)") (class "Default")
      (node (ref "IC4") (pin "11") (pinfunction "PB5_11") (pintype "bidirectional"))
    )
    (net (code "68") (name "unconnected-(IC4-PB6-Pad12)") (class "Default")
      (node (ref "IC4") (pin "12") (pinfunction "PB6_12") (pintype "bidirectional"))
    )
    (net (code "69") (name "unconnected-(IC4-PB7-Pad13)") (class "Default")
      (node (ref "IC4") (pin "13") (pinfunction "PB7_13") (pintype "bidirectional"))
    )
    (net (code "70") (name "unconnected-(IC4-PC0-Pad16)") (class "Default")
      (node (ref "IC4") (pin "16") (pinfunction "PC0_16") (pintype "bidirectional"))
    )
    (net (code "71") (name "unconnected-(IC4-PC1-Pad17)") (class "Default")
      (node (ref "IC4") (pin "17") (pinfunction "PC1_17") (pintype "bidirectional"))
    )
    (net (code "72") (name "unconnected-(IC4-PD3-Pad29)") (class "Default")
      (node (ref "IC4") (pin "29") (pinfunction "PD3_29") (pintype "bidirectional"))
    )
    (net (code "73") (name "unconnected-(IC4-PD4-Pad30)") (class "Default")
      (node (ref "IC4") (pin "30") (pinfunction "PD4_30") (pintype "bidirectional"))
    )
    (net (code "74") (name "unconnected-(IC4-PE3-Pad39)") (class "Default")
      (node (ref "IC4") (pin "39") (pinfunction "PE3_39") (pintype "bidirectional"))
    )
    (net (code "75") (name "unconnected-(IC4-PE4-Pad40)") (class "Default")
      (node (ref "IC4") (pin "40") (pinfunction "PE4_40") (pintype "bidirectional"))
    )
    (net (code "76") (name "unconnected-(IC4-PF3-Pad49)") (class "Default")
      (node (ref "IC4") (pin "49") (pinfunction "PF3_49") (pintype "bidirectional"))
    )
    (net (code "77") (name "unconnected-(IC4-PF4-Pad50)") (class "Default")
      (node (ref "IC4") (pin "50") (pinfunction "PF4_50") (pintype "bidirectional"))
    )
    (net (code "78") (name "unconnected-(JP1-Pad3)") (class "Default")
      (node (ref "JP1") (pin "3") (pinfunction "3_3") (pintype "passive"))
    )
    (net (code "79") (name "unconnected-(JP1-Pad4)") (class "Default")
      (node (ref "JP1") (pin "4") (pinfunction "4_4") (pintype "passive"))
    )
  )
)
